# lpg_v22_4hp.net
KiCad netlist of a schematic drawn in EAGLE
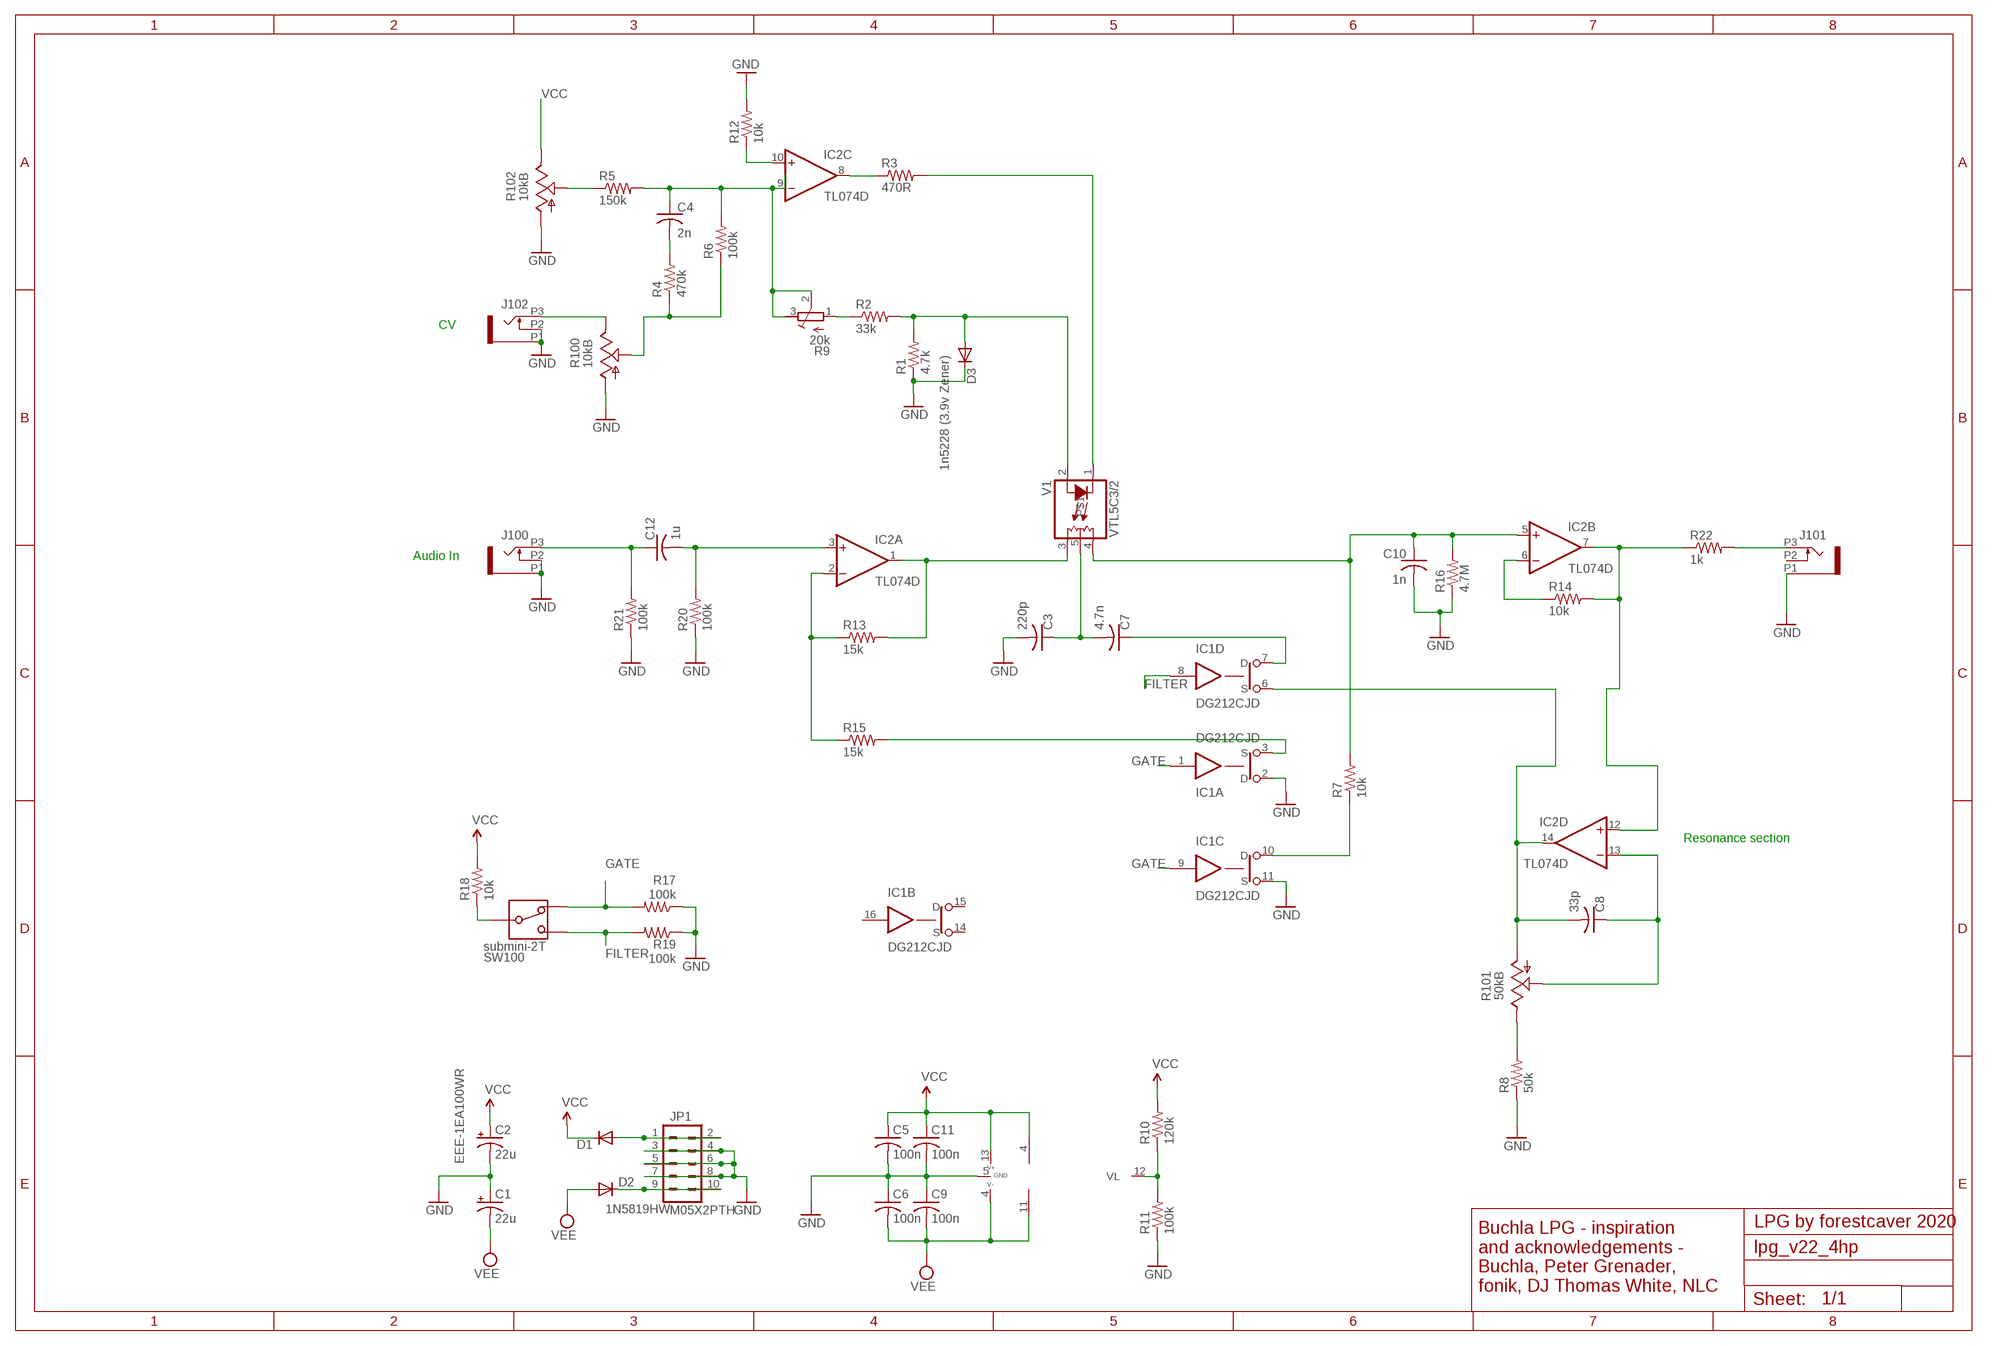
[diagram p0: schematic, sheet 1]

(export (version "E")
  (design (tool "Eeschema 10.0.6"))
  (components
    (comp (ref "C1")
      (value "22u")
      (footprint "eagle-import:PANASONIC_B")
      (fields (field (name "MPN") "EEE-FT1V220AR"))
      (libsource (lib "eagle-import") (part "CPOL-USB"))
    )
    (comp (ref "C2")
      (value "22u")
      (footprint "eagle-import:PANASONIC_B")
      (fields (field (name "MPN") "EEE-FT1V220AR"))
      (libsource (lib "eagle-import") (part "CPOL-USB"))
    )
    (comp (ref "C3")
      (value "220p")
      (footprint "eagle-import:C0603")
      (libsource (lib "eagle-import") (part "rcl_334_C-USC0603"))
    )
    (comp (ref "C4")
      (value "2n")
      (footprint "eagle-import:C0603")
      (libsource (lib "eagle-import") (part "rcl_334_C-USC0603"))
    )
    (comp (ref "C5")
      (value "100n")
      (footprint "eagle-import:C0603")
      (libsource (lib "eagle-import") (part "C-USC0603"))
    )
    (comp (ref "C6")
      (value "100n")
      (footprint "eagle-import:C0603")
      (libsource (lib "eagle-import") (part "C-USC0603"))
    )
    (comp (ref "C7")
      (value "4.7n")
      (footprint "eagle-import:C0603")
      (libsource (lib "eagle-import") (part "rcl_334_C-USC0603"))
    )
    (comp (ref "C8")
      (value "33p")
      (footprint "eagle-import:C0603")
      (libsource (lib "eagle-import") (part "rcl_334_C-USC0603"))
    )
    (comp (ref "C9")
      (value "100n")
      (footprint "eagle-import:C0603")
      (libsource (lib "eagle-import") (part "C-USC0603"))
    )
    (comp (ref "C10")
      (value "1n")
      (footprint "eagle-import:C0603")
      (libsource (lib "eagle-import") (part "rcl_334_C-USC0603"))
    )
    (comp (ref "C11")
      (value "100n")
      (footprint "eagle-import:C0603")
      (libsource (lib "eagle-import") (part "C-USC0603"))
    )
    (comp (ref "C12")
      (value "1u")
      (footprint "eagle-import:C0603")
      (libsource (lib "eagle-import") (part "rcl_334_C-USC0603"))
    )
    (comp (ref "D1")
      (value "1N5819HW")
      (footprint "eagle-import:SOD123")
      (libsource (lib "eagle-import") (part "DIODE-SOD123"))
    )
    (comp (ref "D2")
      (value "1N5819HW")
      (footprint "eagle-import:SOD123")
      (libsource (lib "eagle-import") (part "DIODE-SOD123"))
    )
    (comp (ref "D3")
      (value "1n5228 (3.9v Zener)")
      (footprint "eagle-import:SOD123")
      (fields (field (name "MPN") "MMSZ5228BT1G"))
      (libsource (lib "eagle-import") (part "DIODE-SOD123"))
    )
    (comp (ref "IC1")
      (value "DG212CJD")
      (footprint "eagle-import:SO16")
      (fields (field (name "MOUSER") "584-ADG212AKRZ-R") (field (name "MPN") "ADG212AKRZ-REEL"))
      (libsource (lib "eagle-import") (part "DG212CJD"))
    )
    (comp (ref "IC2")
      (value "TL074D")
      (footprint "eagle-import:SO14")
      (fields (field (name "MOUSER") "595-TL074CDR") (field (name "MPN") "TL074CDR"))
      (libsource (lib "eagle-import") (part "TL074D"))
    )
    (comp (ref "J100")
      (value "PJ301_THONKICONN6")
      (footprint "eagle-import:WQP_PJ_301M6")
      (libsource (lib "eagle-import") (part "PJ301_THONKICONN6"))
    )
    (comp (ref "J101")
      (value "PJ301_THONKICONN6")
      (footprint "eagle-import:WQP_PJ_301M6")
      (libsource (lib "eagle-import") (part "PJ301_THONKICONN6"))
    )
    (comp (ref "J102")
      (value "PJ301_THONKICONN6")
      (footprint "eagle-import:WQP_PJ_301M6")
      (libsource (lib "eagle-import") (part "PJ301_THONKICONN6"))
    )
    (comp (ref "JP1")
      (value "M05X2PTH")
      (footprint "eagle-import:AVR_ICSP")
      (libsource (lib "eagle-import") (part "M05X2PTH"))
    )
    (comp (ref "R1")
      (value "4.7k")
      (footprint "eagle-import:R0603")
      (libsource (lib "eagle-import") (part "R-US_R0603"))
    )
    (comp (ref "R2")
      (value "33k")
      (footprint "eagle-import:R0603")
      (libsource (lib "eagle-import") (part "R-US_R0603"))
    )
    (comp (ref "R3")
      (value "470R")
      (footprint "eagle-import:R0603")
      (libsource (lib "eagle-import") (part "R-US_R0603"))
    )
    (comp (ref "R4")
      (value "470k")
      (footprint "eagle-import:R0603")
      (libsource (lib "eagle-import") (part "R-US_R0603"))
    )
    (comp (ref "R5")
      (value "150k")
      (footprint "eagle-import:R0603")
      (libsource (lib "eagle-import") (part "R-US_R0603"))
    )
    (comp (ref "R6")
      (value "100k")
      (footprint "eagle-import:R0603")
      (libsource (lib "eagle-import") (part "R-US_R0603"))
    )
    (comp (ref "R7")
      (value "10k")
      (footprint "eagle-import:R0603")
      (libsource (lib "eagle-import") (part "R-US_R0603"))
    )
    (comp (ref "R8")
      (value "50k")
      (footprint "eagle-import:R0603")
      (libsource (lib "eagle-import") (part "R-US_R0603"))
    )
    (comp (ref "R9")
      (value "20k")
      (footprint "eagle-import:RTRIM3296X")
      (libsource (lib "eagle-import") (part "R-TRIMM3296X"))
    )
    (comp (ref "R10")
      (value "120k")
      (footprint "eagle-import:R0603")
      (libsource (lib "eagle-import") (part "R-US_R0603"))
    )
    (comp (ref "R11")
      (value "100k")
      (footprint "eagle-import:R0603")
      (libsource (lib "eagle-import") (part "R-US_R0603"))
    )
    (comp (ref "R12")
      (value "10k")
      (footprint "eagle-import:R0603")
      (libsource (lib "eagle-import") (part "R-US_R0603"))
    )
    (comp (ref "R13")
      (value "15k")
      (footprint "eagle-import:R0603")
      (libsource (lib "eagle-import") (part "R-US_R0603"))
    )
    (comp (ref "R14")
      (value "10k")
      (footprint "eagle-import:R0603")
      (libsource (lib "eagle-import") (part "R-US_R0603"))
    )
    (comp (ref "R15")
      (value "15k")
      (footprint "eagle-import:R0603")
      (libsource (lib "eagle-import") (part "R-US_R0603"))
    )
    (comp (ref "R16")
      (value "4.7M")
      (footprint "eagle-import:R0603")
      (libsource (lib "eagle-import") (part "R-US_R0603"))
    )
    (comp (ref "R17")
      (value "100k")
      (footprint "eagle-import:R0603")
      (libsource (lib "eagle-import") (part "R-US_R0603"))
    )
    (comp (ref "R18")
      (value "10k")
      (footprint "eagle-import:R0603")
      (libsource (lib "eagle-import") (part "R-US_R0603"))
    )
    (comp (ref "R19")
      (value "100k")
      (footprint "eagle-import:R0603")
      (libsource (lib "eagle-import") (part "R-US_R0603"))
    )
    (comp (ref "R20")
      (value "100k")
      (footprint "eagle-import:R0603")
      (libsource (lib "eagle-import") (part "R-US_R0603"))
    )
    (comp (ref "R21")
      (value "100k")
      (footprint "eagle-import:R0603")
      (libsource (lib "eagle-import") (part "R-US_R0603"))
    )
    (comp (ref "R22")
      (value "1k")
      (footprint "eagle-import:R0603")
      (libsource (lib "eagle-import") (part "R-US_R0603"))
    )
    (comp (ref "R100")
      (value "10kB")
      (footprint "eagle-import:ALPS_POT_VERTICAL_PS")
      (libsource (lib "eagle-import") (part "POT_USVERTICAL_PS"))
    )
    (comp (ref "R101")
      (value "50kB")
      (footprint "eagle-import:ALPS_POT_VERTICAL_PS")
      (libsource (lib "eagle-import") (part "POT_USVERTICAL_PS"))
    )
    (comp (ref "R102")
      (value "10kB")
      (footprint "eagle-import:ALPS_POT_VERTICAL_PS")
      (libsource (lib "eagle-import") (part "POT_USVERTICAL_PS"))
    )
    (comp (ref "SW100")
      (value "submini-2T")
      (footprint "eagle-import:SPDT-SUB")
      (libsource (lib "eagle-import") (part "SPDTT"))
    )
    (comp (ref "V1")
      (value "VTL5C3/2")
      (footprint "eagle-import:VACTROL_5PIN_VTL5C-2")
      (libsource (lib "eagle-import") (part "VACTROL_5PIN"))
    )
  )
  (nets
    (net (code "1") (name "/FILTER") (class "Default")
      (node (ref "IC1") (pin "8") (pinfunction "IN_8") (pintype "input"))
      (node (ref "R19") (pin "2") (pinfunction "2_2") (pintype "passive"))
      (node (ref "SW100") (pin "P$1") (pinfunction "P$1_P$1") (pintype "passive"))
    )
    (net (code "2") (name "/GATE") (class "Default")
      (node (ref "IC1") (pin "1") (pinfunction "IN_1") (pintype "input"))
      (node (ref "IC1") (pin "9") (pinfunction "IN_9") (pintype "input"))
      (node (ref "R17") (pin "2") (pinfunction "2_2") (pintype "passive"))
      (node (ref "SW100") (pin "P$3") (pinfunction "P$3_P$3") (pintype "passive"))
    )
    (net (code "3") (name "GND") (class "Default")
      (node (ref "C1") (pin "+") (pinfunction "+_+") (pintype "passive"))
      (node (ref "C10") (pin "2") (pinfunction "2_2") (pintype "passive"))
      (node (ref "C11") (pin "2") (pinfunction "2_2") (pintype "passive"))
      (node (ref "C2") (pin "-") (pinfunction "-_-") (pintype "passive"))
      (node (ref "C3") (pin "2") (pinfunction "2_2") (pintype "passive"))
      (node (ref "C5") (pin "2") (pinfunction "2_2") (pintype "passive"))
      (node (ref "C6") (pin "1") (pinfunction "1_1") (pintype "passive"))
      (node (ref "C9") (pin "1") (pinfunction "1_1") (pintype "passive"))
      (node (ref "D3") (pin "C") (pinfunction "C_C") (pintype "passive"))
      (node (ref "IC1") (pin "11") (pinfunction "S_11") (pintype "bidirectional"))
      (node (ref "IC1") (pin "2") (pinfunction "D_2") (pintype "bidirectional"))
      (node (ref "IC1") (pin "5") (pinfunction "GND_5") (pintype "power_in"))
      (node (ref "J100") (pin "P1") (pinfunction "1_P1") (pintype "passive"))
      (node (ref "J100") (pin "P2") (pinfunction "2_P2") (pintype "passive"))
      (node (ref "J101") (pin "P1") (pinfunction "1_P1") (pintype "passive"))
      (node (ref "J102") (pin "P1") (pinfunction "1_P1") (pintype "passive"))
      (node (ref "J102") (pin "P2") (pinfunction "2_P2") (pintype "passive"))
      (node (ref "JP1") (pin "3") (pinfunction "3_3") (pintype "passive"))
      (node (ref "JP1") (pin "4") (pinfunction "4_4") (pintype "passive"))
      (node (ref "JP1") (pin "5") (pinfunction "5_5") (pintype "passive"))
      (node (ref "JP1") (pin "6") (pinfunction "6_6") (pintype "passive"))
      (node (ref "JP1") (pin "7") (pinfunction "7_7") (pintype "passive"))
      (node (ref "JP1") (pin "8") (pinfunction "8_8") (pintype "passive"))
      (node (ref "R1") (pin "1") (pinfunction "1_1") (pintype "passive"))
      (node (ref "R100") (pin "P$3") (pinfunction "A_P$3") (pintype "passive"))
      (node (ref "R102") (pin "P$3") (pinfunction "A_P$3") (pintype "passive"))
      (node (ref "R11") (pin "1") (pinfunction "1_1") (pintype "passive"))
      (node (ref "R12") (pin "2") (pinfunction "2_2") (pintype "passive"))
      (node (ref "R16") (pin "1") (pinfunction "1_1") (pintype "passive"))
      (node (ref "R17") (pin "1") (pinfunction "1_1") (pintype "passive"))
      (node (ref "R19") (pin "1") (pinfunction "1_1") (pintype "passive"))
      (node (ref "R20") (pin "1") (pinfunction "1_1") (pintype "passive"))
      (node (ref "R21") (pin "1") (pinfunction "1_1") (pintype "passive"))
      (node (ref "R8") (pin "1") (pinfunction "1_1") (pintype "passive"))
    )
    (net (code "4") (name "Net-(C4-Pad2)") (class "Default")
      (node (ref "C4") (pin "2") (pinfunction "2_2") (pintype "passive"))
      (node (ref "R4") (pin "2") (pinfunction "2_2") (pintype "passive"))
    )
    (net (code "5") (name "Net-(D1-PadA)") (class "Default")
      (node (ref "D1") (pin "A") (pinfunction "A_A") (pintype "passive"))
      (node (ref "JP1") (pin "1") (pinfunction "1_1") (pintype "passive"))
      (node (ref "JP1") (pin "2") (pinfunction "2_2") (pintype "passive"))
    )
    (net (code "6") (name "Net-(D2-PadC)") (class "Default")
      (node (ref "D2") (pin "C") (pinfunction "C_C") (pintype "passive"))
      (node (ref "JP1") (pin "10") (pinfunction "10_10") (pintype "passive"))
      (node (ref "JP1") (pin "9") (pinfunction "9_9") (pintype "passive"))
    )
    (net (code "7") (name "Net-(IC1A-S)") (class "Default")
      (node (ref "IC1") (pin "3") (pinfunction "S_3") (pintype "bidirectional"))
      (node (ref "R15") (pin "2") (pinfunction "2_2") (pintype "passive"))
    )
    (net (code "8") (name "Net-(IC1C-D)") (class "Default")
      (node (ref "IC1") (pin "10") (pinfunction "D_10") (pintype "bidirectional"))
      (node (ref "R7") (pin "1") (pinfunction "1_1") (pintype "passive"))
    )
    (net (code "9") (name "Net-(IC1D-D)") (class "Default")
      (node (ref "C7") (pin "1") (pinfunction "1_1") (pintype "passive"))
      (node (ref "IC1") (pin "7") (pinfunction "D_7") (pintype "bidirectional"))
    )
    (net (code "10") (name "Net-(IC1D-S)") (class "Default")
      (node (ref "C8") (pin "2") (pinfunction "2_2") (pintype "passive"))
      (node (ref "IC1") (pin "6") (pinfunction "S_6") (pintype "bidirectional"))
      (node (ref "IC2") (pin "14") (pinfunction "OUT_14") (pintype "output"))
      (node (ref "R101") (pin "P$3") (pinfunction "A_P$3") (pintype "passive"))
    )
    (net (code "11") (name "Net-(IC1F-VL)") (class "Default")
      (node (ref "IC1") (pin "12") (pinfunction "VL_12") (pintype "input"))
      (node (ref "R10") (pin "1") (pinfunction "1_1") (pintype "passive"))
      (node (ref "R11") (pin "2") (pinfunction "2_2") (pintype "passive"))
    )
    (net (code "12") (name "Net-(IC2A-+IN)") (class "Default")
      (node (ref "C12") (pin "2") (pinfunction "2_2") (pintype "passive"))
      (node (ref "IC2") (pin "3") (pinfunction "+IN_3") (pintype "input"))
      (node (ref "R20") (pin "2") (pinfunction "2_2") (pintype "passive"))
    )
    (net (code "13") (name "Net-(IC2A--IN)") (class "Default")
      (node (ref "IC2") (pin "2") (pinfunction "-IN_2") (pintype "input"))
      (node (ref "R13") (pin "1") (pinfunction "1_1") (pintype "passive"))
      (node (ref "R15") (pin "1") (pinfunction "1_1") (pintype "passive"))
    )
    (net (code "14") (name "Net-(IC2A-OUT)") (class "Default")
      (node (ref "IC2") (pin "1") (pinfunction "OUT_1") (pintype "output"))
      (node (ref "R13") (pin "2") (pinfunction "2_2") (pintype "passive"))
      (node (ref "V1") (pin "3") (pinfunction "L1_3") (pintype "passive"))
    )
    (net (code "15") (name "Net-(IC2B-+IN)") (class "Default")
      (node (ref "C10") (pin "1") (pinfunction "1_1") (pintype "passive"))
      (node (ref "IC2") (pin "5") (pinfunction "+IN_5") (pintype "input"))
      (node (ref "R16") (pin "2") (pinfunction "2_2") (pintype "passive"))
      (node (ref "R7") (pin "2") (pinfunction "2_2") (pintype "passive"))
      (node (ref "V1") (pin "4") (pinfunction "L2_4") (pintype "passive"))
    )
    (net (code "16") (name "Net-(IC2B--IN)") (class "Default")
      (node (ref "IC2") (pin "6") (pinfunction "-IN_6") (pintype "input"))
      (node (ref "R14") (pin "1") (pinfunction "1_1") (pintype "passive"))
    )
    (net (code "17") (name "Net-(IC2B-OUT)") (class "Default")
      (node (ref "IC2") (pin "12") (pinfunction "+IN_12") (pintype "input"))
      (node (ref "IC2") (pin "7") (pinfunction "OUT_7") (pintype "output"))
      (node (ref "R14") (pin "2") (pinfunction "2_2") (pintype "passive"))
      (node (ref "R22") (pin "1") (pinfunction "1_1") (pintype "passive"))
    )
    (net (code "18") (name "Net-(IC2C-+IN)") (class "Default")
      (node (ref "IC2") (pin "10") (pinfunction "+IN_10") (pintype "input"))
      (node (ref "R12") (pin "1") (pinfunction "1_1") (pintype "passive"))
    )
    (net (code "19") (name "Net-(IC2C--IN)") (class "Default")
      (node (ref "C4") (pin "1") (pinfunction "1_1") (pintype "passive"))
      (node (ref "IC2") (pin "9") (pinfunction "-IN_9") (pintype "input"))
      (node (ref "R5") (pin "2") (pinfunction "2_2") (pintype "passive"))
      (node (ref "R6") (pin "2") (pinfunction "2_2") (pintype "passive"))
      (node (ref "R9") (pin "2") (pinfunction "S_2") (pintype "passive"))
      (node (ref "R9") (pin "3") (pinfunction "A_3") (pintype "passive"))
    )
    (net (code "20") (name "Net-(IC2C-OUT)") (class "Default")
      (node (ref "IC2") (pin "8") (pinfunction "OUT_8") (pintype "output"))
      (node (ref "R3") (pin "1") (pinfunction "1_1") (pintype "passive"))
    )
    (net (code "21") (name "Net-(IC2D--IN)") (class "Default")
      (node (ref "C8") (pin "1") (pinfunction "1_1") (pintype "passive"))
      (node (ref "IC2") (pin "13") (pinfunction "-IN_13") (pintype "input"))
      (node (ref "R101") (pin "P$2") (pinfunction "S_P$2") (pintype "passive"))
    )
    (net (code "22") (name "Net-(J100-3)") (class "Default")
      (node (ref "C12") (pin "1") (pinfunction "1_1") (pintype "passive"))
      (node (ref "J100") (pin "P3") (pinfunction "3_P3") (pintype "passive"))
      (node (ref "R21") (pin "2") (pinfunction "2_2") (pintype "passive"))
    )
    (net (code "23") (name "Net-(J101-3)") (class "Default")
      (node (ref "J101") (pin "P3") (pinfunction "3_P3") (pintype "passive"))
      (node (ref "R22") (pin "2") (pinfunction "2_2") (pintype "passive"))
    )
    (net (code "24") (name "Net-(J102-3)") (class "Default")
      (node (ref "J102") (pin "P3") (pinfunction "3_P3") (pintype "passive"))
      (node (ref "R100") (pin "P$1") (pinfunction "E_P$1") (pintype "passive"))
    )
    (net (code "25") (name "Net-(R9-E)") (class "Default")
      (node (ref "R2") (pin "1") (pinfunction "1_1") (pintype "passive"))
      (node (ref "R9") (pin "1") (pinfunction "E_1") (pintype "passive"))
    )
    (net (code "26") (name "Net-(R18-Pad1)") (class "Default")
      (node (ref "R18") (pin "1") (pinfunction "1_1") (pintype "passive"))
      (node (ref "SW100") (pin "P$2") (pinfunction "P$2_P$2") (pintype "passive"))
    )
    (net (code "27") (name "Net-(R100-S)") (class "Default")
      (node (ref "R100") (pin "P$2") (pinfunction "S_P$2") (pintype "passive"))
      (node (ref "R4") (pin "1") (pinfunction "1_1") (pintype "passive"))
      (node (ref "R6") (pin "1") (pinfunction "1_1") (pintype "passive"))
    )
    (net (code "28") (name "Net-(R101-E)") (class "Default")
      (node (ref "R101") (pin "P$1") (pinfunction "E_P$1") (pintype "passive"))
      (node (ref "R8") (pin "2") (pinfunction "2_2") (pintype "passive"))
    )
    (net (code "29") (name "Net-(R102-S)") (class "Default")
      (node (ref "R102") (pin "P$2") (pinfunction "S_P$2") (pintype "passive"))
      (node (ref "R5") (pin "1") (pinfunction "1_1") (pintype "passive"))
    )
    (net (code "30") (name "Net-(V1-A)") (class "Default")
      (node (ref "D3") (pin "A") (pinfunction "A_A") (pintype "passive"))
      (node (ref "R1") (pin "2") (pinfunction "2_2") (pintype "passive"))
      (node (ref "R2") (pin "2") (pinfunction "2_2") (pintype "passive"))
      (node (ref "V1") (pin "2") (pinfunction "A_2") (pintype "passive"))
    )
    (net (code "31") (name "Net-(V1-C)") (class "Default")
      (node (ref "R3") (pin "2") (pinfunction "2_2") (pintype "passive"))
      (node (ref "V1") (pin "1") (pinfunction "C_1") (pintype "passive"))
    )
    (net (code "32") (name "Net-(V1-P$1)") (class "Default")
      (node (ref "C3") (pin "1") (pinfunction "1_1") (pintype "passive"))
      (node (ref "C7") (pin "2") (pinfunction "2_2") (pintype "passive"))
      (node (ref "V1") (pin "5") (pinfunction "P$1_5") (pintype "passive"))
    )
    (net (code "33") (name "VCC") (class "Default")
      (node (ref "C11") (pin "1") (pinfunction "1_1") (pintype "passive"))
      (node (ref "C2") (pin "+") (pinfunction "+_+") (pintype "passive"))
      (node (ref "C5") (pin "1") (pinfunction "1_1") (pintype "passive"))
      (node (ref "D1") (pin "C") (pinfunction "C_C") (pintype "passive"))
      (node (ref "IC1") (pin "13") (pinfunction "V+_13") (pintype "power_in"))
      (node (ref "IC2") (pin "4") (pinfunction "V+_4") (pintype "power_in"))
      (node (ref "R10") (pin "2") (pinfunction "2_2") (pintype "passive"))
      (node (ref "R102") (pin "P$1") (pinfunction "E_P$1") (pintype "passive"))
      (node (ref "R18") (pin "2") (pinfunction "2_2") (pintype "passive"))
    )
    (net (code "34") (name "VEE") (class "Default")
      (node (ref "C1") (pin "-") (pinfunction "-_-") (pintype "passive"))
      (node (ref "C6") (pin "2") (pinfunction "2_2") (pintype "passive"))
      (node (ref "C9") (pin "2") (pinfunction "2_2") (pintype "passive"))
      (node (ref "D2") (pin "A") (pinfunction "A_A") (pintype "passive"))
      (node (ref "IC1") (pin "4") (pinfunction "V-_4") (pintype "power_in"))
      (node (ref "IC2") (pin "11") (pinfunction "V-_11") (pintype "power_in"))
    )
    (net (code "35") (name "unconnected-(IC1B-D-Pad15)") (class "Default")
      (node (ref "IC1") (pin "15") (pinfunction "D_15") (pintype "bidirectional"))
    )
    (net (code "36") (name "unconnected-(IC1B-IN-Pad16)") (class "Default")
      (node (ref "IC1") (pin "16") (pinfunction "IN_16") (pintype "input"))
    )
    (net (code "37") (name "unconnected-(IC1B-S-Pad14)") (class "Default")
      (node (ref "IC1") (pin "14") (pinfunction "S_14") (pintype "bidirectional"))
    )
    (net (code "38") (name "unconnected-(J101-2-PadP2)") (class "Default")
      (node (ref "J101") (pin "P2") (pinfunction "2_P2") (pintype "passive"))
    )
  )
)
